# analog.net
KiCad netlist of a schematic drawn in Altium Designer
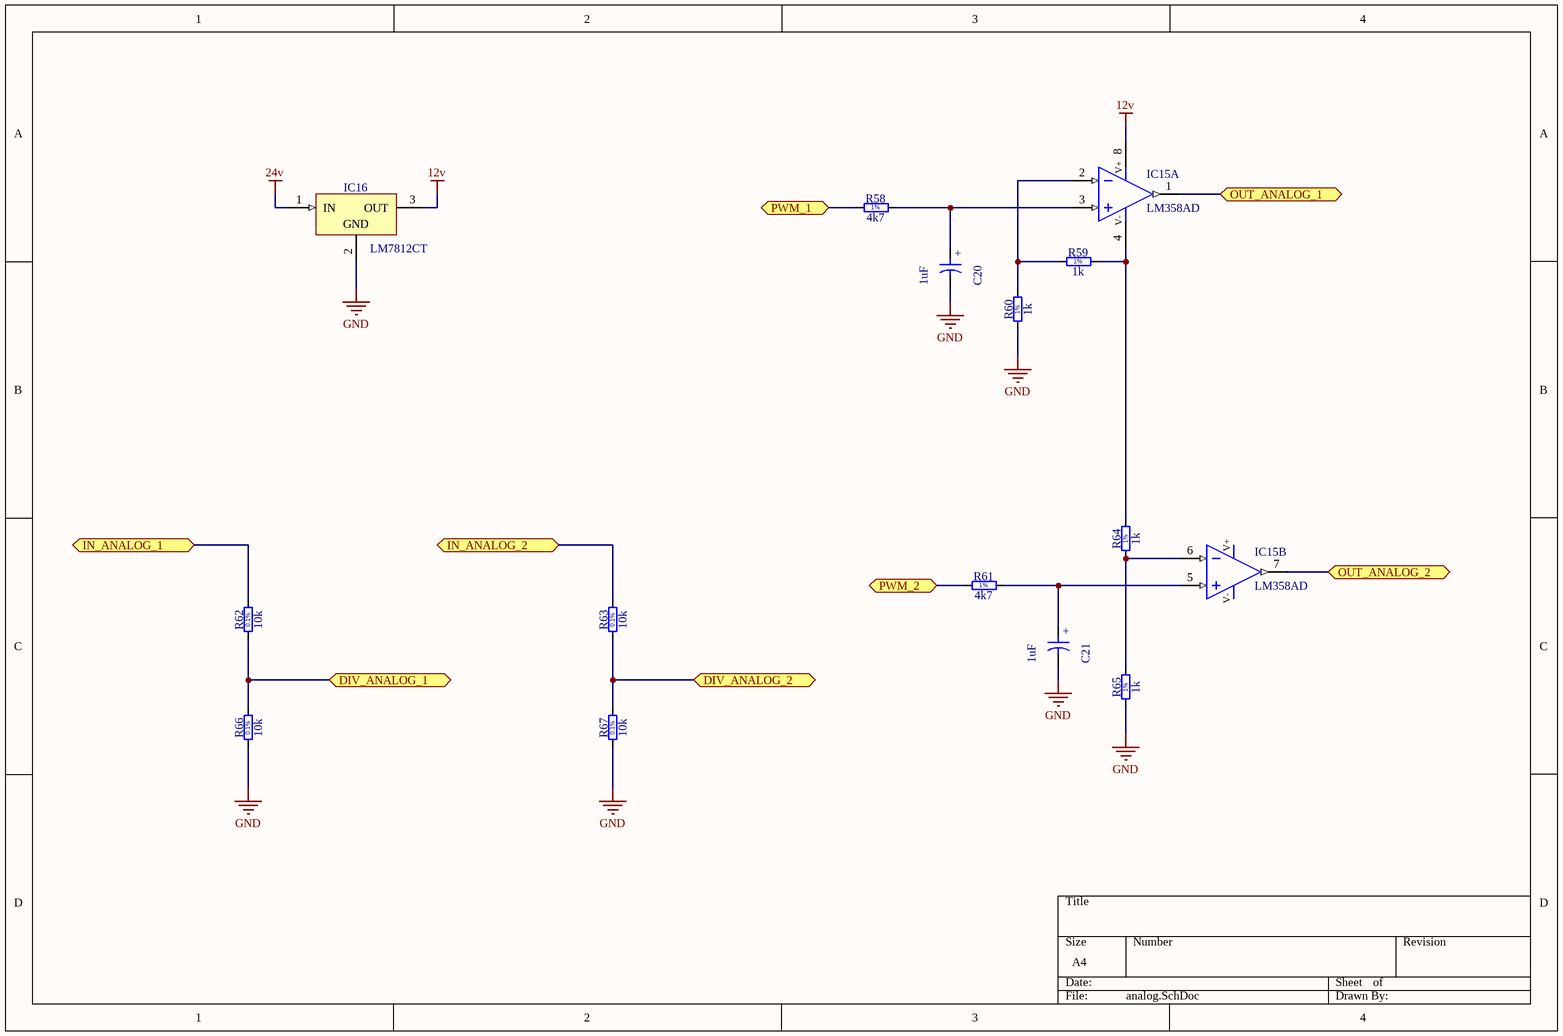
[diagram p0: analog.SchDoc]

(export (version "E")
  (design (tool "Eeschema 10.0.6"))
  (components
    (comp (ref "C20")
      (value "1uF")
      (footprint "CAPPRB254-450X710")
      (description "Polarised capacitor")
      (fields
        (field (name "PART NUMBER") "CTEB_1UF_35V_10%_254-450X710")
        (field (name "VOLTAGE") "35V")
        (field (name "AUTHOR") "CERN DEM JLC")
      )
      (libsource (lib "Capacitors") (part "Capacitor - polarized"))
    )
    (comp (ref "C21")
      (value "1uF")
      (footprint "CAPPRB254-450X710")
      (description "Polarised capacitor")
      (fields
        (field (name "PART NUMBER") "CTEB_1UF_35V_10%_254-450X710")
        (field (name "VOLTAGE") "35V")
        (field (name "AUTHOR") "CERN DEM JLC")
      )
      (libsource (lib "Capacitors") (part "Capacitor - polarized"))
    )
    (comp (ref "IC15")
      (value "LM358AD")
      (footprint "SOIC127P600X175-8N")
      (description "Dual Operational Amplifier")
      (fields (field (name "MANUFACTURER") "TEXAS INSTRUMENTS") (field (name "AUTHOR") "CERN DEM JLC"))
      (libsource (lib "ICs And Semiconductors") (part "Operational Amplifier x2 Type1"))
    )
    (comp (ref "IC16")
      (value "LM7812CT")
      (footprint "TO-220-V")
      (description "3-Terminal Regulator 1=IN 2=GND 3=OUT")
      (fields
        (field (name "PART NUMBER") "LM7812CT_v")
        (field (name "MANUFACTURER") "FAIRCHILD SEMICONDUCTOR")
        (field (name "AUTHOR") "CERN DEM JLC")
      )
      (libsource (lib "ICs And Semiconductors") (part "REG3 1IN-2GND-3OUT"))
    )
    (comp (ref "R58")
      (value "4k7")
      (footprint "RESC2012X60N")
      (description "Resistor - 1%")
      (fields
        (field (name "PART NUMBER") "R0805_4K7_1%_0.125W_100PPM")
        (field (name "POWER") "0.125W")
        (field (name "AUTHOR") "CERN DEM JLC")
      )
      (libsource (lib "Resistors") (part "Resistor - 1%"))
    )
    (comp (ref "R59")
      (value "1k")
      (footprint "RESC2012X60N")
      (description "Resistor - 1%")
      (fields
        (field (name "PART NUMBER") "R0805_1K_1%_0.33W_100PPM_VISHAY_CRCW-HP")
        (field (name "POWER") "0.33W")
        (field (name "AUTHOR") "CERN DEM JLC")
      )
      (libsource (lib "Resistors") (part "Resistor - 1%"))
    )
    (comp (ref "R60")
      (value "1k")
      (footprint "RESC2012X60N")
      (description "Resistor - 1%")
      (fields
        (field (name "PART NUMBER") "R0805_1K_1%_0.33W_100PPM_VISHAY_CRCW-HP")
        (field (name "POWER") "0.33W")
        (field (name "AUTHOR") "CERN DEM JLC")
      )
      (libsource (lib "Resistors") (part "Resistor - 1%"))
    )
    (comp (ref "R61")
      (value "4k7")
      (footprint "RESC2012X60N")
      (description "Resistor - 1%")
      (fields
        (field (name "PART NUMBER") "R0805_4K7_1%_0.125W_100PPM")
        (field (name "POWER") "0.125W")
        (field (name "AUTHOR") "CERN DEM JLC")
      )
      (libsource (lib "Resistors") (part "Resistor - 1%"))
    )
    (comp (ref "R62")
      (value "10k")
      (footprint "RESC2012X60N")
      (description "Resistor - 0.1%")
      (fields
        (field (name "PART NUMBER") "R0805_10K_0.1%_0.1W_10PPM")
        (field (name "POWER") "0.1W")
        (field (name "AUTHOR") "CERN DEM JLC")
      )
      (libsource (lib "Resistors") (part "Resistor - 0.1%"))
    )
    (comp (ref "R63")
      (value "10k")
      (footprint "RESC2012X60N")
      (description "Resistor - 0.1%")
      (fields
        (field (name "PART NUMBER") "R0805_10K_0.1%_0.1W_10PPM")
        (field (name "POWER") "0.1W")
        (field (name "AUTHOR") "CERN DEM JLC")
      )
      (libsource (lib "Resistors") (part "Resistor - 0.1%"))
    )
    (comp (ref "R64")
      (value "1k")
      (footprint "RESC2012X60N")
      (description "Resistor - 1%")
      (fields
        (field (name "PART NUMBER") "R0805_1K_1%_0.33W_100PPM_VISHAY_CRCW-HP")
        (field (name "POWER") "0.33W")
        (field (name "AUTHOR") "CERN DEM JLC")
      )
      (libsource (lib "Resistors") (part "Resistor - 1%"))
    )
    (comp (ref "R65")
      (value "1k")
      (footprint "RESC2012X60N")
      (description "Resistor - 1%")
      (fields
        (field (name "PART NUMBER") "R0805_1K_1%_0.33W_100PPM_VISHAY_CRCW-HP")
        (field (name "POWER") "0.33W")
        (field (name "AUTHOR") "CERN DEM JLC")
      )
      (libsource (lib "Resistors") (part "Resistor - 1%"))
    )
    (comp (ref "R66")
      (value "10k")
      (footprint "RESC2012X60N")
      (description "Resistor - 0.1%")
      (fields
        (field (name "PART NUMBER") "R0805_10K_0.1%_0.1W_10PPM")
        (field (name "POWER") "0.1W")
        (field (name "AUTHOR") "CERN DEM JLC")
      )
      (libsource (lib "Resistors") (part "Resistor - 0.1%"))
    )
    (comp (ref "R67")
      (value "10k")
      (footprint "RESC2012X60N")
      (description "Resistor - 0.1%")
      (fields
        (field (name "PART NUMBER") "R0805_10K_0.1%_0.1W_10PPM")
        (field (name "POWER") "0.1W")
        (field (name "AUTHOR") "CERN DEM JLC")
      )
      (libsource (lib "Resistors") (part "Resistor - 0.1%"))
    )
  )
  (nets
    (net (code "1") (name "/DIV_ANALOG_1") (class "Default")
      (node (ref "R62") (pin "1") (pinfunction "1_1") (pintype "passive"))
      (node (ref "R66") (pin "2") (pinfunction "2_2") (pintype "passive"))
    )
    (net (code "2") (name "/DIV_ANALOG_2") (class "Default")
      (node (ref "R63") (pin "1") (pinfunction "1_1") (pintype "passive"))
      (node (ref "R67") (pin "2") (pinfunction "2_2") (pintype "passive"))
    )
    (net (code "3") (name "/IN_ANALOG_1") (class "Default")
      (node (ref "R62") (pin "2") (pinfunction "2_2") (pintype "passive"))
    )
    (net (code "4") (name "/IN_ANALOG_2") (class "Default")
      (node (ref "R63") (pin "2") (pinfunction "2_2") (pintype "passive"))
    )
    (net (code "5") (name "/OUT_ANALOG_1") (class "Default")
      (node (ref "IC15") (pin "1") (pinfunction "OUT_1") (pintype "output"))
    )
    (net (code "6") (name "/OUT_ANALOG_2") (class "Default")
      (node (ref "IC15") (pin "7") (pinfunction "OUT_7") (pintype "output"))
    )
    (net (code "7") (name "/PWM_1") (class "Default")
      (node (ref "R58") (pin "1") (pinfunction "1_1") (pintype "passive"))
    )
    (net (code "8") (name "/PWM_2") (class "Default")
      (node (ref "R61") (pin "1") (pinfunction "1_1") (pintype "passive"))
    )
    (net (code "9") (name "12v") (class "Default")
      (node (ref "IC15") (pin "8") (pinfunction "V+_8") (pintype "power_in"))
      (node (ref "IC16") (pin "3") (pinfunction "OUT_3") (pintype "power_in"))
    )
    (net (code "10") (name "24v") (class "Default")
      (node (ref "IC16") (pin "1") (pinfunction "IN_1") (pintype "input"))
    )
    (net (code "11") (name "GND") (class "Default")
      (node (ref "C20") (pin "2") (pinfunction "2_2") (pintype "passive"))
      (node (ref "C21") (pin "2") (pinfunction "2_2") (pintype "passive"))
      (node (ref "IC16") (pin "2") (pinfunction "GND_2") (pintype "power_in"))
      (node (ref "R60") (pin "1") (pinfunction "1_1") (pintype "passive"))
      (node (ref "R65") (pin "1") (pinfunction "1_1") (pintype "passive"))
      (node (ref "R66") (pin "1") (pinfunction "1_1") (pintype "passive"))
      (node (ref "R67") (pin "1") (pinfunction "1_1") (pintype "passive"))
    )
    (net (code "12") (name "Net-(IC15A-IN+)") (class "Default")
      (node (ref "C20") (pin "1") (pinfunction "1_1") (pintype "passive"))
      (node (ref "IC15") (pin "3") (pinfunction "IN+_3") (pintype "input"))
      (node (ref "R58") (pin "2") (pinfunction "2_2") (pintype "passive"))
    )
    (net (code "13") (name "Net-(IC15A-IN-)") (class "Default")
      (node (ref "IC15") (pin "2") (pinfunction "IN-_2") (pintype "input"))
      (node (ref "R59") (pin "1") (pinfunction "1_1") (pintype "passive"))
      (node (ref "R60") (pin "2") (pinfunction "2_2") (pintype "passive"))
    )
    (net (code "14") (name "Net-(IC15B-IN+)") (class "Default")
      (node (ref "C21") (pin "1") (pinfunction "1_1") (pintype "passive"))
      (node (ref "IC15") (pin "5") (pinfunction "IN+_5") (pintype "input"))
      (node (ref "R61") (pin "2") (pinfunction "2_2") (pintype "passive"))
    )
    (net (code "15") (name "Net-(IC15B-IN-)") (class "Default")
      (node (ref "IC15") (pin "6") (pinfunction "IN-_6") (pintype "input"))
      (node (ref "R64") (pin "1") (pinfunction "1_1") (pintype "passive"))
      (node (ref "R65") (pin "2") (pinfunction "2_2") (pintype "passive"))
    )
    (net (code "16") (name "V-") (class "Default")
      (node (ref "IC15") (pin "4") (pinfunction "V-_4") (pintype "power_in"))
      (node (ref "R59") (pin "2") (pinfunction "2_2") (pintype "passive"))
      (node (ref "R64") (pin "2") (pinfunction "2_2") (pintype "passive"))
    )
  )
)
